# A06_LINKS_POWER.net
KiCad netlist of a schematic drawn in Altium Designer
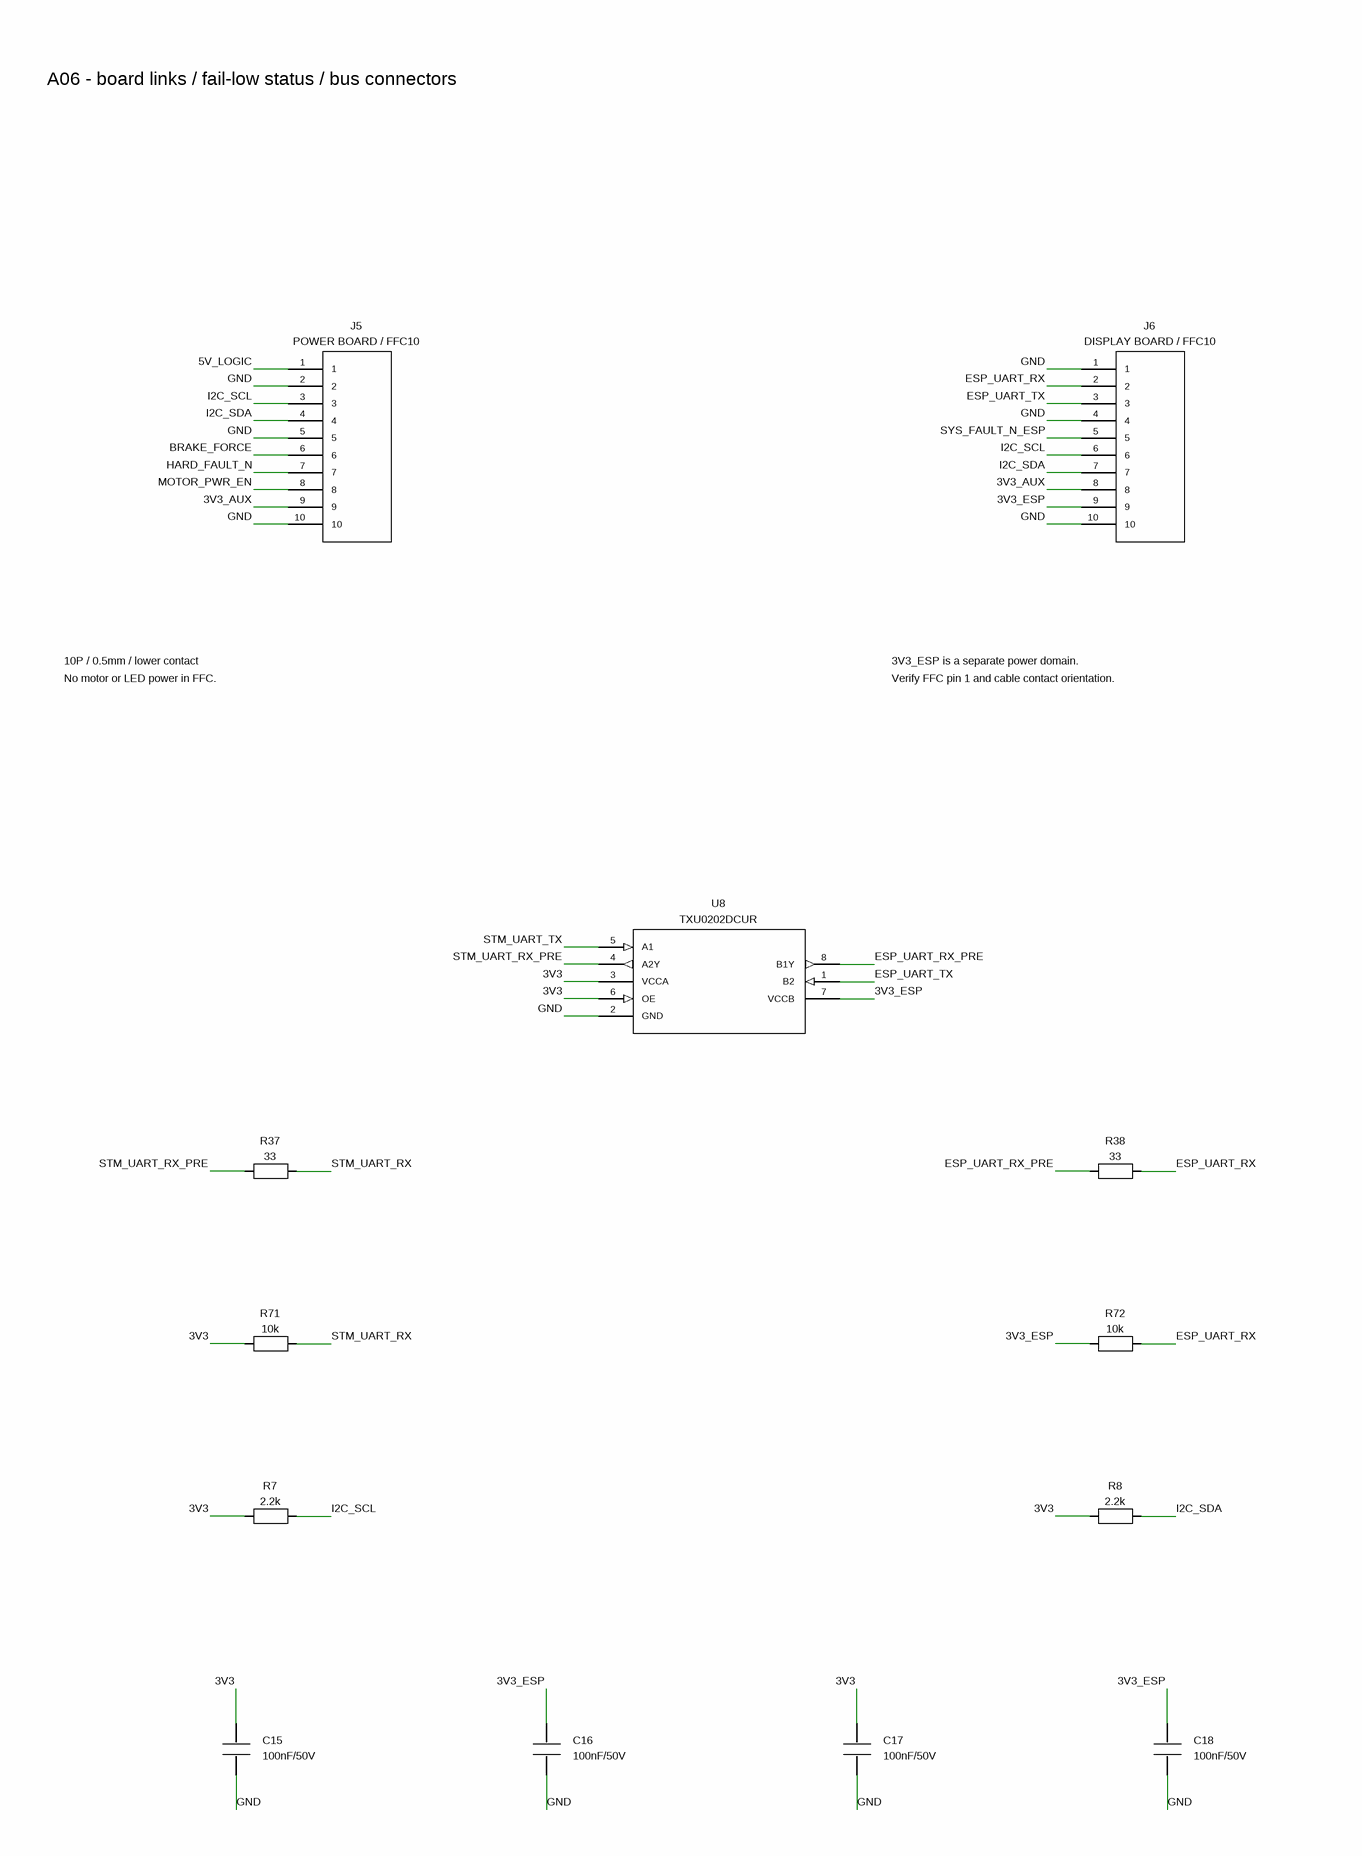
[diagram p0: A06_LINKS_POWER.SchDoc, left]
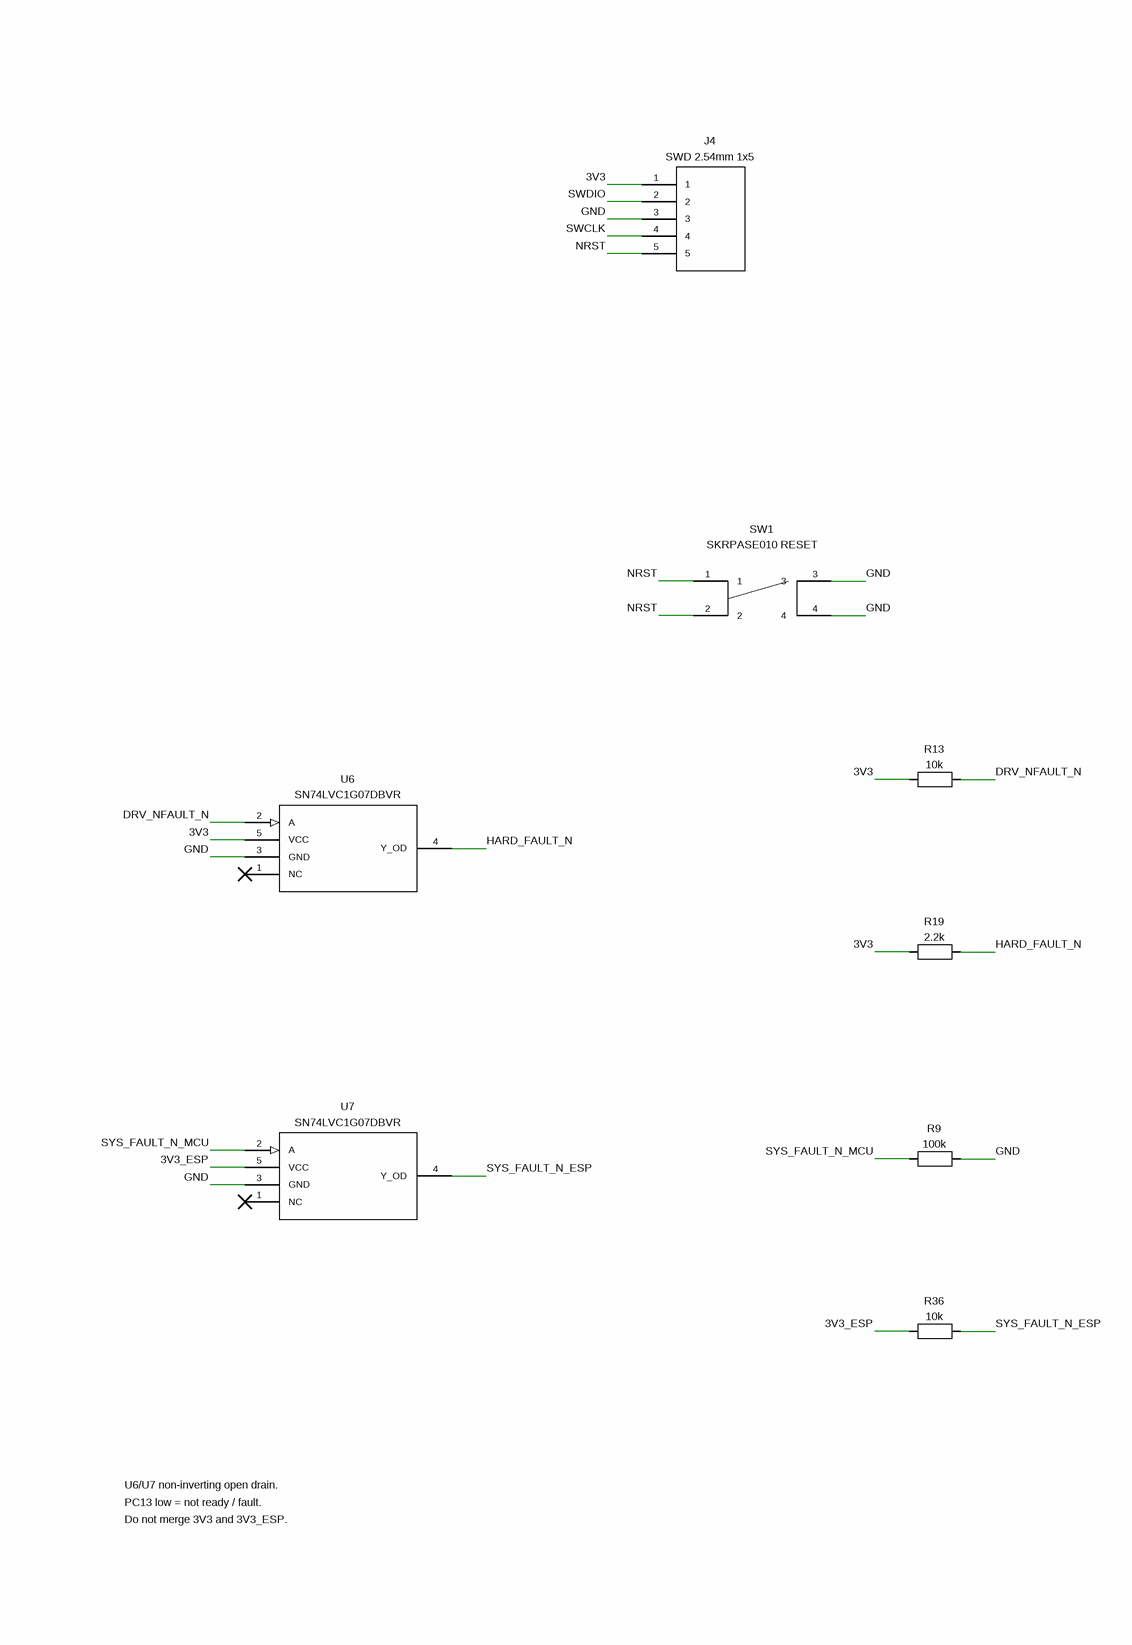
[diagram p1: A06_LINKS_POWER.SchDoc, right]

(export (version "E")
  (design (tool "Eeschema 10.0.6"))
  (components
    (comp (ref "C15")
      (value "100nF/50V")
      (footprint "User_STM32F407_Ctrl:C0603_M")
      (description "电容")
      (fields (field (name "MPN") "CL10B104KB8NNNC"))
      (libsource (lib "altium-import") (part "root_0_C_"))
    )
    (comp (ref "C16")
      (value "100nF/50V")
      (footprint "User_STM32F407_Ctrl:C0603_M")
      (description "电容")
      (fields (field (name "MPN") "CL10B104KB8NNNC"))
      (libsource (lib "altium-import") (part "root_0_C_"))
    )
    (comp (ref "C17")
      (value "100nF/50V")
      (footprint "User_STM32F407_Ctrl:C0603_M")
      (description "电容")
      (fields (field (name "MPN") "CL10B104KB8NNNC"))
      (libsource (lib "altium-import") (part "root_0_C_"))
    )
    (comp (ref "C18")
      (value "100nF/50V")
      (footprint "User_STM32F407_Ctrl:C0603_M")
      (description "电容")
      (fields (field (name "MPN") "CL10B104KB8NNNC"))
      (libsource (lib "altium-import") (part "root_0_C_"))
    )
    (comp (ref "J4")
      (value "SWD 2.54mm 1x5")
      (footprint "GL30_J4_Header:GL30_HDR_1X05_P254_D102")
      (description "SWD调试口")
      (fields (field (name "MPN") "通用单排排针 1×5P 2.54mm 直插"))
      (libsource (lib "altium-import") (part "root_0_Connector_5_"))
    )
    (comp (ref "J5")
      (value "POWER BOARD / FFC10")
      (footprint "User_SamacSys:FH1210S05SH55")
      (description "A↔B 电源板FFC")
      (fields (field (name "MPN") "FH12-10S-0.5SH(55)"))
      (libsource (lib "altium-import") (part "root_0_Connector_10_"))
    )
    (comp (ref "J6")
      (value "DISPLAY BOARD / FFC10")
      (footprint "User_SamacSys:FH1210S05SH55")
      (description "A↔C 屏幕与传感器FFC")
      (fields (field (name "MPN") "FH12-10S-0.5SH(55)"))
      (libsource (lib "altium-import") (part "root_0_Connector_10_"))
    )
    (comp (ref "R7")
      (value "2.2k")
      (footprint "User_STM32F407_Ctrl:R0603_M")
      (description "电阻")
      (fields (field (name "MPN") "通用厚膜 2.2k 1% 0.1 W"))
      (libsource (lib "altium-import") (part "root_1_R_"))
    )
    (comp (ref "R8")
      (value "2.2k")
      (footprint "User_STM32F407_Ctrl:R0603_M")
      (description "电阻")
      (fields (field (name "MPN") "通用厚膜 2.2k 1% 0.1 W"))
      (libsource (lib "altium-import") (part "root_1_R_"))
    )
    (comp (ref "R9")
      (value "100k")
      (footprint "User_STM32F407_Ctrl:R0603_M")
      (description "电阻")
      (fields (field (name "MPN") "通用厚膜 100k 1% 0.1 W"))
      (libsource (lib "altium-import") (part "root_1_R_"))
    )
    (comp (ref "R13")
      (value "10k")
      (footprint "User_STM32F407_Ctrl:R0603_M")
      (description "电阻")
      (fields (field (name "MPN") "通用厚膜 10k 1% 0.1 W"))
      (libsource (lib "altium-import") (part "root_1_R_"))
    )
    (comp (ref "R19")
      (value "2.2k")
      (footprint "User_STM32F407_Ctrl:R0603_M")
      (description "电阻")
      (fields (field (name "MPN") "通用厚膜 2.2k 1% 0.1 W"))
      (libsource (lib "altium-import") (part "root_1_R_"))
    )
    (comp (ref "R36")
      (value "10k")
      (footprint "User_STM32F407_Ctrl:R0603_M")
      (description "电阻")
      (fields (field (name "MPN") "通用厚膜 10k 1% 0.1 W"))
      (libsource (lib "altium-import") (part "root_1_R_"))
    )
    (comp (ref "R37")
      (value "33")
      (footprint "User_STM32F407_Ctrl:R0603_M")
      (description "电阻")
      (fields (field (name "MPN") "通用厚膜 33 1% 0.1 W"))
      (libsource (lib "altium-import") (part "root_1_R_"))
    )
    (comp (ref "R38")
      (value "33")
      (footprint "User_STM32F407_Ctrl:R0603_M")
      (description "电阻")
      (fields (field (name "MPN") "通用厚膜 33 1% 0.1 W"))
      (libsource (lib "altium-import") (part "root_1_R_"))
    )
    (comp (ref "R71")
      (value "10k")
      (footprint "User_STM32F407_Ctrl:R0603_M")
      (description "电阻")
      (fields (field (name "MPN") "通用厚膜 10k 1% 0.1 W"))
      (libsource (lib "altium-import") (part "root_1_R_"))
    )
    (comp (ref "R72")
      (value "10k")
      (footprint "User_STM32F407_Ctrl:R0603_M")
      (description "电阻")
      (fields (field (name "MPN") "通用厚膜 10k 1% 0.1 W"))
      (libsource (lib "altium-import") (part "root_1_R_"))
    )
    (comp (ref "SW1")
      (value "SKRPASE010 RESET")
      (footprint "User_SamacSys:SKRPASE010")
      (description "复位按键")
      (fields (field (name "MPN") "SKRPASE010"))
      (libsource (lib "altium-import") (part "root_0_SKRPASE010_"))
    )
    (comp (ref "U6")
      (value "SN74LVC1G07DBVR")
      (footprint "User_SamacSys:SOT95P280X145-5N")
      (description "DRV故障开漏缓冲")
      (libsource (lib "altium-import") (part "root_0_SN74LVC1G07DBVR_"))
    )
    (comp (ref "U7")
      (value "SN74LVC1G07DBVR")
      (footprint "User_SamacSys:SOT95P280X145-5N")
      (description "ESP故障开漏缓冲")
      (libsource (lib "altium-import") (part "root_0_SN74LVC1G07DBVR_"))
    )
    (comp (ref "U8")
      (value "TXU0202DCUR")
      (footprint "User_SamacSys:SOP50P310X90-8N")
      (description "UART双电源接口")
      (libsource (lib "altium-import") (part "root_0_TXU0202DCUR_"))
    )
  )
  (nets
    (net (code "1") (name "/3V3") (class "Default")
      (node (ref "C15") (pin "1") (pintype "passive"))
      (node (ref "C17") (pin "1") (pintype "passive"))
      (node (ref "J4") (pin "1") (pinfunction "1_1") (pintype "passive"))
      (node (ref "R13") (pin "1") (pintype "passive"))
      (node (ref "R19") (pin "1") (pintype "passive"))
      (node (ref "R7") (pin "1") (pintype "passive"))
      (node (ref "R71") (pin "1") (pintype "passive"))
      (node (ref "R8") (pin "1") (pintype "passive"))
      (node (ref "U6") (pin "5") (pinfunction "VCC_5") (pintype "power_in"))
      (node (ref "U8") (pin "3") (pinfunction "VCCA_3") (pintype "power_in"))
      (node (ref "U8") (pin "6") (pinfunction "OE_6") (pintype "input"))
    )
    (net (code "2") (name "/3V3_AUX") (class "Default")
      (node (ref "J5") (pin "9") (pinfunction "9_9") (pintype "passive"))
      (node (ref "J6") (pin "8") (pinfunction "8_8") (pintype "passive"))
    )
    (net (code "3") (name "/3V3_ESP") (class "Default")
      (node (ref "C16") (pin "1") (pintype "passive"))
      (node (ref "C18") (pin "1") (pintype "passive"))
      (node (ref "J6") (pin "9") (pinfunction "9_9") (pintype "passive"))
      (node (ref "R36") (pin "1") (pintype "passive"))
      (node (ref "R72") (pin "1") (pintype "passive"))
      (node (ref "U7") (pin "5") (pinfunction "VCC_5") (pintype "power_in"))
      (node (ref "U8") (pin "7") (pinfunction "VCCB_7") (pintype "power_in"))
    )
    (net (code "4") (name "/5V_LOGIC") (class "Default")
      (node (ref "J5") (pin "1") (pinfunction "1_1") (pintype "passive"))
    )
    (net (code "5") (name "/BRAKE_FORCE") (class "Default")
      (node (ref "J5") (pin "6") (pinfunction "6_6") (pintype "passive"))
    )
    (net (code "6") (name "/DRV_NFAULT_N") (class "Default")
      (node (ref "R13") (pin "2") (pintype "passive"))
      (node (ref "U6") (pin "2") (pinfunction "A_2") (pintype "input"))
    )
    (net (code "7") (name "/ESP_UART_RX") (class "Default")
      (node (ref "J6") (pin "2") (pinfunction "2_2") (pintype "passive"))
      (node (ref "R38") (pin "2") (pintype "passive"))
      (node (ref "R72") (pin "2") (pintype "passive"))
    )
    (net (code "8") (name "/ESP_UART_RX_PRE") (class "Default")
      (node (ref "R38") (pin "1") (pintype "passive"))
      (node (ref "U8") (pin "8") (pinfunction "B1Y_8") (pintype "output"))
    )
    (net (code "9") (name "/ESP_UART_TX") (class "Default")
      (node (ref "J6") (pin "3") (pinfunction "3_3") (pintype "passive"))
      (node (ref "U8") (pin "1") (pinfunction "B2_1") (pintype "input"))
    )
    (net (code "10") (name "/GND") (class "Default")
      (node (ref "C15") (pin "2") (pintype "passive"))
      (node (ref "C16") (pin "2") (pintype "passive"))
      (node (ref "C17") (pin "2") (pintype "passive"))
      (node (ref "C18") (pin "2") (pintype "passive"))
      (node (ref "J4") (pin "3") (pinfunction "3_3") (pintype "passive"))
      (node (ref "J5") (pin "10") (pinfunction "10_10") (pintype "passive"))
      (node (ref "J5") (pin "2") (pinfunction "2_2") (pintype "passive"))
      (node (ref "J5") (pin "5") (pinfunction "5_5") (pintype "passive"))
      (node (ref "J6") (pin "1") (pinfunction "1_1") (pintype "passive"))
      (node (ref "J6") (pin "10") (pinfunction "10_10") (pintype "passive"))
      (node (ref "J6") (pin "4") (pinfunction "4_4") (pintype "passive"))
      (node (ref "R9") (pin "2") (pintype "passive"))
      (node (ref "SW1") (pin "3") (pinfunction "3_3") (pintype "passive"))
      (node (ref "SW1") (pin "4") (pinfunction "4_4") (pintype "passive"))
      (node (ref "U6") (pin "3") (pinfunction "GND_3") (pintype "power_in"))
      (node (ref "U7") (pin "3") (pinfunction "GND_3") (pintype "power_in"))
      (node (ref "U8") (pin "2") (pinfunction "GND_2") (pintype "power_in"))
    )
    (net (code "11") (name "/HARD_FAULT_N") (class "Default")
      (node (ref "J5") (pin "7") (pinfunction "7_7") (pintype "passive"))
      (node (ref "R19") (pin "2") (pintype "passive"))
      (node (ref "U6") (pin "4") (pinfunction "Y_OD_4") (pintype "open_collector"))
    )
    (net (code "12") (name "/I2C_SCL") (class "Default")
      (node (ref "J5") (pin "3") (pinfunction "3_3") (pintype "passive"))
      (node (ref "J6") (pin "6") (pinfunction "6_6") (pintype "passive"))
      (node (ref "R7") (pin "2") (pintype "passive"))
    )
    (net (code "13") (name "/I2C_SDA") (class "Default")
      (node (ref "J5") (pin "4") (pinfunction "4_4") (pintype "passive"))
      (node (ref "J6") (pin "7") (pinfunction "7_7") (pintype "passive"))
      (node (ref "R8") (pin "2") (pintype "passive"))
    )
    (net (code "14") (name "/MOTOR_PWR_EN") (class "Default")
      (node (ref "J5") (pin "8") (pinfunction "8_8") (pintype "passive"))
    )
    (net (code "15") (name "/NRST") (class "Default")
      (node (ref "J4") (pin "5") (pinfunction "5_5") (pintype "passive"))
      (node (ref "SW1") (pin "1") (pinfunction "1_1") (pintype "passive"))
      (node (ref "SW1") (pin "2") (pinfunction "2_2") (pintype "passive"))
    )
    (net (code "16") (name "/STM_UART_RX") (class "Default")
      (node (ref "R37") (pin "2") (pintype "passive"))
      (node (ref "R71") (pin "2") (pintype "passive"))
    )
    (net (code "17") (name "/STM_UART_RX_PRE") (class "Default")
      (node (ref "R37") (pin "1") (pintype "passive"))
      (node (ref "U8") (pin "4") (pinfunction "A2Y_4") (pintype "output"))
    )
    (net (code "18") (name "/STM_UART_TX") (class "Default")
      (node (ref "U8") (pin "5") (pinfunction "A1_5") (pintype "input"))
    )
    (net (code "19") (name "/SWCLK") (class "Default")
      (node (ref "J4") (pin "4") (pinfunction "4_4") (pintype "passive"))
    )
    (net (code "20") (name "/SWDIO") (class "Default")
      (node (ref "J4") (pin "2") (pinfunction "2_2") (pintype "passive"))
    )
    (net (code "21") (name "/SYS_FAULT_N_ESP") (class "Default")
      (node (ref "J6") (pin "5") (pinfunction "5_5") (pintype "passive"))
      (node (ref "R36") (pin "2") (pintype "passive"))
      (node (ref "U7") (pin "4") (pinfunction "Y_OD_4") (pintype "open_collector"))
    )
    (net (code "22") (name "/SYS_FAULT_N_MCU") (class "Default")
      (node (ref "R9") (pin "1") (pintype "passive"))
      (node (ref "U7") (pin "2") (pinfunction "A_2") (pintype "input"))
    )
    (net (code "23") (name "unconnected-(U6-NC-Pad1)") (class "Default")
      (node (ref "U6") (pin "1") (pinfunction "NC_1") (pintype "passive+no_connect"))
    )
    (net (code "24") (name "unconnected-(U7-NC-Pad1)") (class "Default")
      (node (ref "U7") (pin "1") (pinfunction "NC_1") (pintype "passive+no_connect"))
    )
  )
)
